# OpenPack_BATMOD_V1p0_USBA.net
KiCad netlist of a schematic drawn in Altium Designer
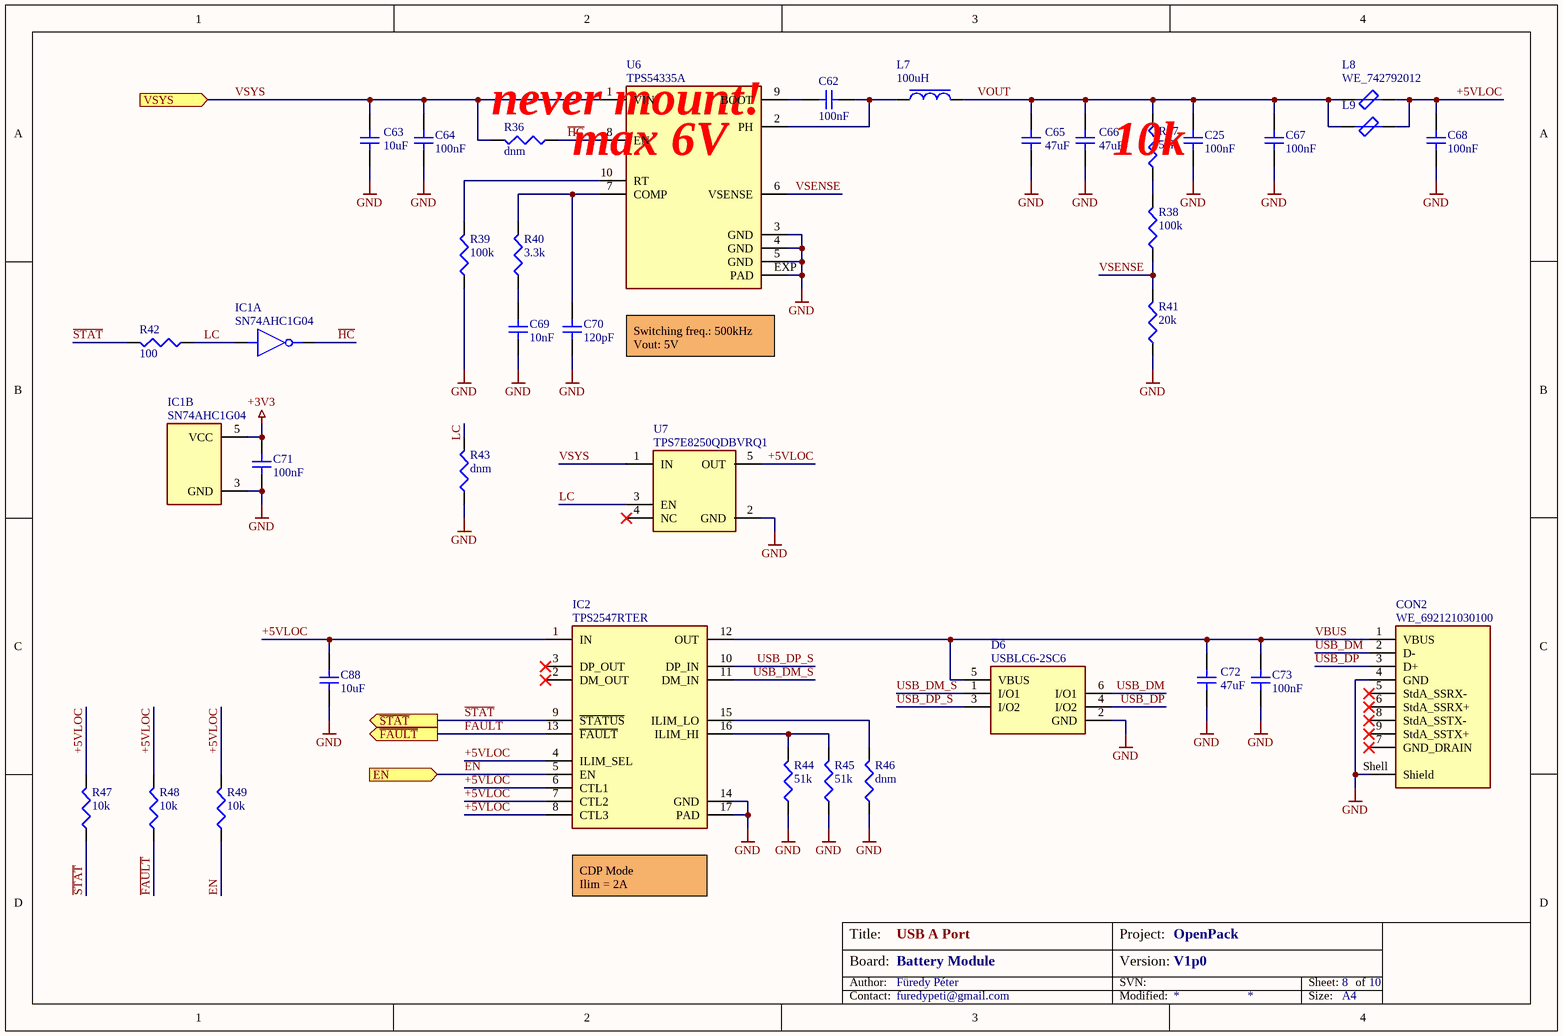
[diagram p0: OpenPack_BATMOD_V1p0_USBA.SchDoc]

(export (version "E")
  (design (tool "Eeschema 10.0.6"))
  (components
    (comp (ref "C25")
      (value "100nF")
      (footprint "CAP_0603")
      (description "MLCC capacitor")
      (libsource (lib "SCHLIB") (part "NP-CAPACITOR"))
    )
    (comp (ref "C62")
      (value "100nF")
      (footprint "CAP_0603")
      (description "MLCC capacitor")
      (libsource (lib "SCHLIB") (part "NP-CAPACITOR"))
    )
    (comp (ref "C63")
      (value "10uF")
      (footprint "CAP_1210")
      (description "UMK325BJ106KM-P")
      (fields (field (name "PART NUMBER") "810-CGA6P1X7R1N106K2"))
      (libsource (lib "SCHLIB") (part "NP-CAPACITOR"))
    )
    (comp (ref "C64")
      (value "100nF")
      (footprint "CAP_0603")
      (description "MLCC capacitor")
      (libsource (lib "SCHLIB") (part "NP-CAPACITOR"))
    )
    (comp (ref "C65")
      (value "47uF")
      (footprint "CAP_1210")
      (description "Np-Cap")
      (fields (field (name "PART NUMBER") "80-C1210C476M4P"))
      (libsource (lib "SCHLIB") (part "NP-CAPACITOR"))
    )
    (comp (ref "C66")
      (value "47uF")
      (footprint "CAP_1210")
      (description "Np-Cap")
      (fields (field (name "PART NUMBER") "80-C1210C476M4P"))
      (libsource (lib "SCHLIB") (part "NP-CAPACITOR"))
    )
    (comp (ref "C67")
      (value "100nF")
      (footprint "CAP_0603")
      (description "MLCC capacitor")
      (libsource (lib "SCHLIB") (part "NP-CAPACITOR"))
    )
    (comp (ref "C68")
      (value "100nF")
      (footprint "CAP_0603")
      (description "MLCC capacitor")
      (libsource (lib "SCHLIB") (part "NP-CAPACITOR"))
    )
    (comp (ref "C69")
      (value "10nF")
      (footprint "CAP_0603")
      (description "MLCC capacitor")
      (libsource (lib "SCHLIB") (part "NP-CAPACITOR"))
    )
    (comp (ref "C70")
      (value "120pF")
      (footprint "CAP_0603")
      (description "MLCC capacitor")
      (libsource (lib "SCHLIB") (part "NP-CAPACITOR"))
    )
    (comp (ref "C71")
      (value "100nF")
      (footprint "CAP_0603")
      (description "MLCC capacitor")
      (libsource (lib "SCHLIB") (part "NP-CAPACITOR"))
    )
    (comp (ref "C72")
      (value "47uF")
      (footprint "CAP_1210")
      (description "Np-Cap")
      (fields (field (name "PART NUMBER") "80-C1210C476M4P"))
      (libsource (lib "SCHLIB") (part "NP-CAPACITOR"))
    )
    (comp (ref "C73")
      (value "100nF")
      (footprint "CAP_0603")
      (description "MLCC capacitor")
      (libsource (lib "SCHLIB") (part "NP-CAPACITOR"))
    )
    (comp (ref "C88")
      (value "10uF")
      (footprint "CAP_0603")
      (description "MLCC capacitor")
      (libsource (lib "SCHLIB") (part "NP-CAPACITOR"))
    )
    (comp (ref "CON2")
      (value "WE_692121030100")
      (footprint "WE_692121030100")
      (description "USB Connectors WR-COM 3.0 TypeA SMT 9Pin Horztl Female")
      (fields (field (name "PART NUMBER") "710-692121030100"))
      (libsource (lib "SCHLIB") (part "WE_692121030100"))
    )
    (comp (ref "D6")
      (value "USBLC6-2SC6")
      (footprint "SOT-23-6")
      (description "ESD Protection Diodes / TVS Diodes ESD Protection Low Cap")
      (fields (field (name "PART NUMBER") "511-USBLC6-2SC6"))
      (libsource (lib "SCHLIB") (part "USBLC6-2SC6"))
    )
    (comp (ref "IC1")
      (value "SN74AHC1G04")
      (footprint "SC-70-5")
      (description "Signle inverter, 2V-5V")
      (fields (field (name "PART NUMBER") "595-SN74AHC1G04DCKT"))
      (libsource (lib "SCHLIB") (part "SN74AHC1G04"))
    )
    (comp (ref "IC2")
      (value "TPS2547RTER")
      (footprint "QFN-16")
      (description "USB Switch ICs USB charging port co ntroller and 3A pow A 595-TPS2547RTET")
      (fields (field (name "PART NUMBER") "595-TPS2547RTER"))
      (libsource (lib "SCHLIB") (part "TPS2547RTER"))
    )
    (comp (ref "L7")
      (value "100uH")
      (footprint "IND_2")
      (description "Ferrit core coil, 22uH 2.85A, 75mR")
      (fields (field (name "PART NUMBER") "994-MSS1038T-223MLC"))
      (libsource (lib "SCHLIB") (part "Inductance - 22uH"))
    )
    (comp (ref "L8")
      (value "WE_742792012")
      (footprint "IND-0805")
      (description "Chip Ferrite Bead, 33R @100MHz, 4A")
      (fields (field (name "PART NUMBER") "710-742792012"))
      (libsource (lib "SCHLIB") (part "WE_742792012"))
    )
    (comp (ref "L9")
      (value "WE_742792012")
      (footprint "IND-0805")
      (description "Chip Ferrite Bead, 33R @100MHz, 4A")
      (fields (field (name "PART NUMBER") "710-742792012"))
      (libsource (lib "SCHLIB") (part "WE_742792012"))
    )
    (comp (ref "R36")
      (value "dnm")
      (footprint "RES-0603")
      (description "Metal Film Resistor")
      (libsource (lib "SCHLIB") (part "RESISTOR"))
    )
    (comp (ref "R37")
      (value "51k")
      (footprint "RES-0603")
      (description "Metal Film Resistor")
      (libsource (lib "SCHLIB") (part "RESISTOR"))
    )
    (comp (ref "R38")
      (value "100k")
      (footprint "RES-0603")
      (description "Metal Film Resistor")
      (libsource (lib "SCHLIB") (part "RESISTOR"))
    )
    (comp (ref "R39")
      (value "100k")
      (footprint "RES-0603")
      (description "Metal Film Resistor")
      (libsource (lib "SCHLIB") (part "RESISTOR"))
    )
    (comp (ref "R40")
      (value "3.3k")
      (footprint "RES-0603")
      (description "Metal Film Resistor")
      (libsource (lib "SCHLIB") (part "RESISTOR"))
    )
    (comp (ref "R41")
      (value "20k")
      (footprint "RES-0603")
      (description "Metal Film Resistor")
      (libsource (lib "SCHLIB") (part "RESISTOR"))
    )
    (comp (ref "R42")
      (value "100")
      (footprint "RES-0603")
      (description "Metal Film Resistor")
      (libsource (lib "SCHLIB") (part "RESISTOR"))
    )
    (comp (ref "R43")
      (value "dnm")
      (footprint "RES-0603")
      (description "Metal Film Resistor")
      (libsource (lib "SCHLIB") (part "RESISTOR"))
    )
    (comp (ref "R44")
      (value "51k")
      (footprint "RES-0603")
      (description "Metal Film Resistor")
      (libsource (lib "SCHLIB") (part "RESISTOR"))
    )
    (comp (ref "R45")
      (value "51k")
      (footprint "RES-0603")
      (description "Metal Film Resistor")
      (libsource (lib "SCHLIB") (part "RESISTOR"))
    )
    (comp (ref "R46")
      (value "dnm")
      (footprint "RES-0603")
      (description "Metal Film Resistor")
      (libsource (lib "SCHLIB") (part "RESISTOR"))
    )
    (comp (ref "R47")
      (value "10k")
      (footprint "RES-0603")
      (description "Metal Film Resistor")
      (libsource (lib "SCHLIB") (part "RESISTOR"))
    )
    (comp (ref "R48")
      (value "10k")
      (footprint "RES-0603")
      (description "Metal Film Resistor")
      (libsource (lib "SCHLIB") (part "RESISTOR"))
    )
    (comp (ref "R49")
      (value "10k")
      (footprint "RES-0603")
      (description "Metal Film Resistor")
      (libsource (lib "SCHLIB") (part "RESISTOR"))
    )
    (comp (ref "U6")
      (value "TPS54335A")
      (footprint "VSON-10")
      (description "Switching Voltage Regulators 4.5Vto28VInp 3A Sync Step-Down Converter A 595-TPS54335ADRCT")
      (fields (field (name "PART NUMBER") "595-TPS54335ADRCR"))
      (libsource (lib "SCHLIB") (part "TPS54335A"))
    )
    (comp (ref "U7")
      (value "TPS7E8250QDBVRQ1")
      (footprint "SOT-23-5")
      (description "LDO Voltage Regulators 5V, 300mA")
      (fields (field (name "PART NUMBER") "595-TPS7E8250QDBVRQ1"))
      (libsource (lib "SCHLIB") (part "TPS7E8250QDBVRQ1"))
    )
  )
  (nets
    (net (code "1") (name "+3V3") (class "Default")
      (node (ref "C71") (pin "1") (pinfunction "1_1") (pintype "passive"))
      (node (ref "IC1") (pin "5") (pinfunction "VCC_5") (pintype "passive"))
    )
    (net (code "2") (name "/+5VLOC") (class "Default")
      (node (ref "C68") (pin "1") (pinfunction "1_1") (pintype "passive"))
      (node (ref "C88") (pin "2") (pinfunction "2_2") (pintype "passive"))
      (node (ref "IC2") (pin "1") (pinfunction "IN_1") (pintype "passive"))
      (node (ref "IC2") (pin "4") (pinfunction "ILIM_SEL_4") (pintype "passive"))
      (node (ref "IC2") (pin "6") (pinfunction "CTL1_6") (pintype "passive"))
      (node (ref "IC2") (pin "7") (pinfunction "CTL2_7") (pintype "passive"))
      (node (ref "IC2") (pin "8") (pinfunction "CTL3_8") (pintype "passive"))
      (node (ref "L8") (pin "2") (pinfunction "2_2") (pintype "passive"))
      (node (ref "L9") (pin "2") (pinfunction "2_2") (pintype "passive"))
      (node (ref "R47") (pin "2") (pintype "passive"))
      (node (ref "R48") (pin "2") (pintype "passive"))
      (node (ref "R49") (pin "2") (pintype "passive"))
      (node (ref "U7") (pin "5") (pinfunction "OUT_5") (pintype "passive"))
    )
    (net (code "3") (name "/EN") (class "Default")
      (node (ref "IC2") (pin "5") (pinfunction "EN_5") (pintype "passive"))
      (node (ref "R49") (pin "1") (pintype "passive"))
    )
    (net (code "4") (name "/LC") (class "Default")
      (node (ref "IC1") (pin "2") (pinfunction "A_2") (pintype "passive"))
      (node (ref "R42") (pin "1") (pintype "passive"))
      (node (ref "R43") (pin "2") (pintype "passive"))
      (node (ref "U7") (pin "3") (pinfunction "EN_3") (pintype "passive"))
    )
    (net (code "5") (name "/USB_DM") (class "Default")
      (node (ref "CON2") (pin "2") (pinfunction "D-_2") (pintype "passive"))
      (node (ref "D6") (pin "6") (pinfunction "I/O1_6") (pintype "passive"))
    )
    (net (code "6") (name "/USB_DM_S") (class "Default")
      (node (ref "D6") (pin "1") (pinfunction "I/O1_1") (pintype "passive"))
      (node (ref "IC2") (pin "11") (pinfunction "DM_IN_11") (pintype "passive"))
    )
    (net (code "7") (name "/USB_DP") (class "Default")
      (node (ref "CON2") (pin "3") (pinfunction "D+_3") (pintype "passive"))
      (node (ref "D6") (pin "4") (pinfunction "I/O2_4") (pintype "passive"))
    )
    (net (code "8") (name "/USB_DP_S") (class "Default")
      (node (ref "D6") (pin "3") (pinfunction "I/O2_3") (pintype "passive"))
      (node (ref "IC2") (pin "10") (pinfunction "DP_IN_10") (pintype "passive"))
    )
    (net (code "9") (name "/VBUS") (class "Default")
      (node (ref "C72") (pin "2") (pinfunction "2_2") (pintype "passive"))
      (node (ref "C73") (pin "1") (pinfunction "1_1") (pintype "passive"))
      (node (ref "CON2") (pin "1") (pinfunction "VBUS_1") (pintype "passive"))
      (node (ref "D6") (pin "5") (pinfunction "VBUS_5") (pintype "passive"))
      (node (ref "IC2") (pin "12") (pinfunction "OUT_12") (pintype "passive"))
    )
    (net (code "10") (name "/VOUT") (class "Default")
      (node (ref "C25") (pin "1") (pinfunction "1_1") (pintype "passive"))
      (node (ref "C65") (pin "2") (pinfunction "2_2") (pintype "passive"))
      (node (ref "C66") (pin "2") (pinfunction "2_2") (pintype "passive"))
      (node (ref "C67") (pin "1") (pinfunction "1_1") (pintype "passive"))
      (node (ref "L7") (pin "2") (pinfunction "2_2") (pintype "passive"))
      (node (ref "L8") (pin "1") (pinfunction "1_1") (pintype "passive"))
      (node (ref "L9") (pin "1") (pinfunction "1_1") (pintype "passive"))
      (node (ref "R37") (pin "2") (pintype "passive"))
    )
    (net (code "11") (name "/VSENSE") (class "Default")
      (node (ref "R38") (pin "1") (pintype "passive"))
      (node (ref "R41") (pin "2") (pintype "passive"))
      (node (ref "U6") (pin "6") (pinfunction "VSENSE_6") (pintype "passive"))
    )
    (net (code "12") (name "/VSYS") (class "Default")
      (node (ref "C63") (pin "2") (pinfunction "2_2") (pintype "passive"))
      (node (ref "C64") (pin "1") (pinfunction "1_1") (pintype "passive"))
      (node (ref "R36") (pin "2") (pintype "passive"))
      (node (ref "U6") (pin "1") (pinfunction "VIN_1") (pintype "passive"))
      (node (ref "U7") (pin "1") (pinfunction "IN_1") (pintype "passive"))
    )
    (net (code "13") (name "/~{FAULT}") (class "Default")
      (node (ref "IC2") (pin "13") (pinfunction "~{FAULT}_13") (pintype "passive"))
      (node (ref "R48") (pin "1") (pintype "passive"))
    )
    (net (code "14") (name "/~{HC}") (class "Default")
      (node (ref "IC1") (pin "4") (pinfunction "Y_4") (pintype "passive"))
      (node (ref "R36") (pin "1") (pintype "passive"))
      (node (ref "U6") (pin "8") (pinfunction "EN_8") (pintype "passive"))
    )
    (net (code "15") (name "/~{STAT}") (class "Default")
      (node (ref "IC2") (pin "9") (pinfunction "~{STATUS}_9") (pintype "passive"))
      (node (ref "R42") (pin "2") (pintype "passive"))
      (node (ref "R47") (pin "1") (pintype "passive"))
    )
    (net (code "16") (name "GND") (class "Default")
      (node (ref "C25") (pin "2") (pinfunction "2_2") (pintype "passive"))
      (node (ref "C63") (pin "1") (pinfunction "1_1") (pintype "passive"))
      (node (ref "C64") (pin "2") (pinfunction "2_2") (pintype "passive"))
      (node (ref "C65") (pin "1") (pinfunction "1_1") (pintype "passive"))
      (node (ref "C66") (pin "1") (pinfunction "1_1") (pintype "passive"))
      (node (ref "C67") (pin "2") (pinfunction "2_2") (pintype "passive"))
      (node (ref "C68") (pin "2") (pinfunction "2_2") (pintype "passive"))
      (node (ref "C69") (pin "2") (pinfunction "2_2") (pintype "passive"))
      (node (ref "C70") (pin "2") (pinfunction "2_2") (pintype "passive"))
      (node (ref "C71") (pin "2") (pinfunction "2_2") (pintype "passive"))
      (node (ref "C72") (pin "1") (pinfunction "1_1") (pintype "passive"))
      (node (ref "C73") (pin "2") (pinfunction "2_2") (pintype "passive"))
      (node (ref "C88") (pin "1") (pinfunction "1_1") (pintype "passive"))
      (node (ref "CON2") (pin "4") (pinfunction "GND_4") (pintype "passive"))
      (node (ref "CON2") (pin "Shell") (pinfunction "Shield_Shell") (pintype "passive"))
      (node (ref "D6") (pin "2") (pinfunction "GND_2") (pintype "passive"))
      (node (ref "IC1") (pin "3") (pinfunction "GND_3") (pintype "passive"))
      (node (ref "IC2") (pin "14") (pinfunction "GND_14") (pintype "passive"))
      (node (ref "IC2") (pin "17") (pinfunction "PAD_17") (pintype "passive"))
      (node (ref "R39") (pin "1") (pintype "passive"))
      (node (ref "R41") (pin "1") (pintype "passive"))
      (node (ref "R43") (pin "1") (pintype "passive"))
      (node (ref "R44") (pin "1") (pintype "passive"))
      (node (ref "R45") (pin "1") (pintype "passive"))
      (node (ref "R46") (pin "1") (pintype "passive"))
      (node (ref "U6") (pin "3") (pinfunction "GND_3") (pintype "passive"))
      (node (ref "U6") (pin "4") (pinfunction "GND_4") (pintype "passive"))
      (node (ref "U6") (pin "5") (pinfunction "GND_5") (pintype "passive"))
      (node (ref "U6") (pin "EXP") (pinfunction "PAD_EXP") (pintype "passive"))
      (node (ref "U7") (pin "2") (pinfunction "GND_2") (pintype "passive"))
    )
    (net (code "17") (name "Net-(C69-Pad1)") (class "Default")
      (node (ref "C69") (pin "1") (pinfunction "1_1") (pintype "passive"))
      (node (ref "R40") (pin "1") (pintype "passive"))
    )
    (net (code "18") (name "Net-(IC2-ILIM_HI)") (class "Default")
      (node (ref "IC2") (pin "16") (pinfunction "ILIM_HI_16") (pintype "passive"))
      (node (ref "R44") (pin "2") (pintype "passive"))
      (node (ref "R45") (pin "2") (pintype "passive"))
    )
    (net (code "19") (name "Net-(IC2-ILIM_LO)") (class "Default")
      (node (ref "IC2") (pin "15") (pinfunction "ILIM_LO_15") (pintype "passive"))
      (node (ref "R46") (pin "2") (pintype "passive"))
    )
    (net (code "20") (name "Net-(R37-Pad1)") (class "Default")
      (node (ref "R37") (pin "1") (pintype "passive"))
      (node (ref "R38") (pin "2") (pintype "passive"))
    )
    (net (code "21") (name "Net-(U6-BOOT)") (class "Default")
      (node (ref "C62") (pin "2") (pinfunction "2_2") (pintype "passive"))
      (node (ref "U6") (pin "9") (pinfunction "BOOT_9") (pintype "passive"))
    )
    (net (code "22") (name "Net-(U6-COMP)") (class "Default")
      (node (ref "C70") (pin "1") (pinfunction "1_1") (pintype "passive"))
      (node (ref "R40") (pin "2") (pintype "passive"))
      (node (ref "U6") (pin "7") (pinfunction "COMP_7") (pintype "passive"))
    )
    (net (code "23") (name "Net-(U6-PH)") (class "Default")
      (node (ref "C62") (pin "1") (pinfunction "1_1") (pintype "passive"))
      (node (ref "L7") (pin "1") (pinfunction "1_1") (pintype "passive"))
      (node (ref "U6") (pin "2") (pinfunction "PH_2") (pintype "passive"))
    )
    (net (code "24") (name "Net-(U6-RT)") (class "Default")
      (node (ref "R39") (pin "2") (pintype "passive"))
      (node (ref "U6") (pin "10") (pinfunction "RT_10") (pintype "passive"))
    )
    (net (code "25") (name "unconnected-(CON2-GND_DRAIN-Pad7)") (class "Default")
      (node (ref "CON2") (pin "7") (pinfunction "GND_DRAIN_7") (pintype "passive+no_connect"))
    )
    (net (code "26") (name "unconnected-(CON2-StdA_SSRX+-Pad6)") (class "Default")
      (node (ref "CON2") (pin "6") (pinfunction "StdA_SSRX+_6") (pintype "passive+no_connect"))
    )
    (net (code "27") (name "unconnected-(CON2-StdA_SSRX--Pad5)") (class "Default")
      (node (ref "CON2") (pin "5") (pinfunction "StdA_SSRX-_5") (pintype "passive+no_connect"))
    )
    (net (code "28") (name "unconnected-(CON2-StdA_SSTX+-Pad9)") (class "Default")
      (node (ref "CON2") (pin "9") (pinfunction "StdA_SSTX+_9") (pintype "passive+no_connect"))
    )
    (net (code "29") (name "unconnected-(CON2-StdA_SSTX--Pad8)") (class "Default")
      (node (ref "CON2") (pin "8") (pinfunction "StdA_SSTX-_8") (pintype "passive+no_connect"))
    )
    (net (code "30") (name "unconnected-(IC2-DM_OUT-Pad2)") (class "Default")
      (node (ref "IC2") (pin "2") (pinfunction "DM_OUT_2") (pintype "passive+no_connect"))
    )
    (net (code "31") (name "unconnected-(IC2-DP_OUT-Pad3)") (class "Default")
      (node (ref "IC2") (pin "3") (pinfunction "DP_OUT_3") (pintype "passive+no_connect"))
    )
    (net (code "32") (name "unconnected-(U7-NC-Pad4)") (class "Default")
      (node (ref "U7") (pin "4") (pinfunction "NC_4") (pintype "passive+no_connect"))
    )
  )
)
